# CPLD.net
KiCad netlist of a schematic drawn in Altium Designer
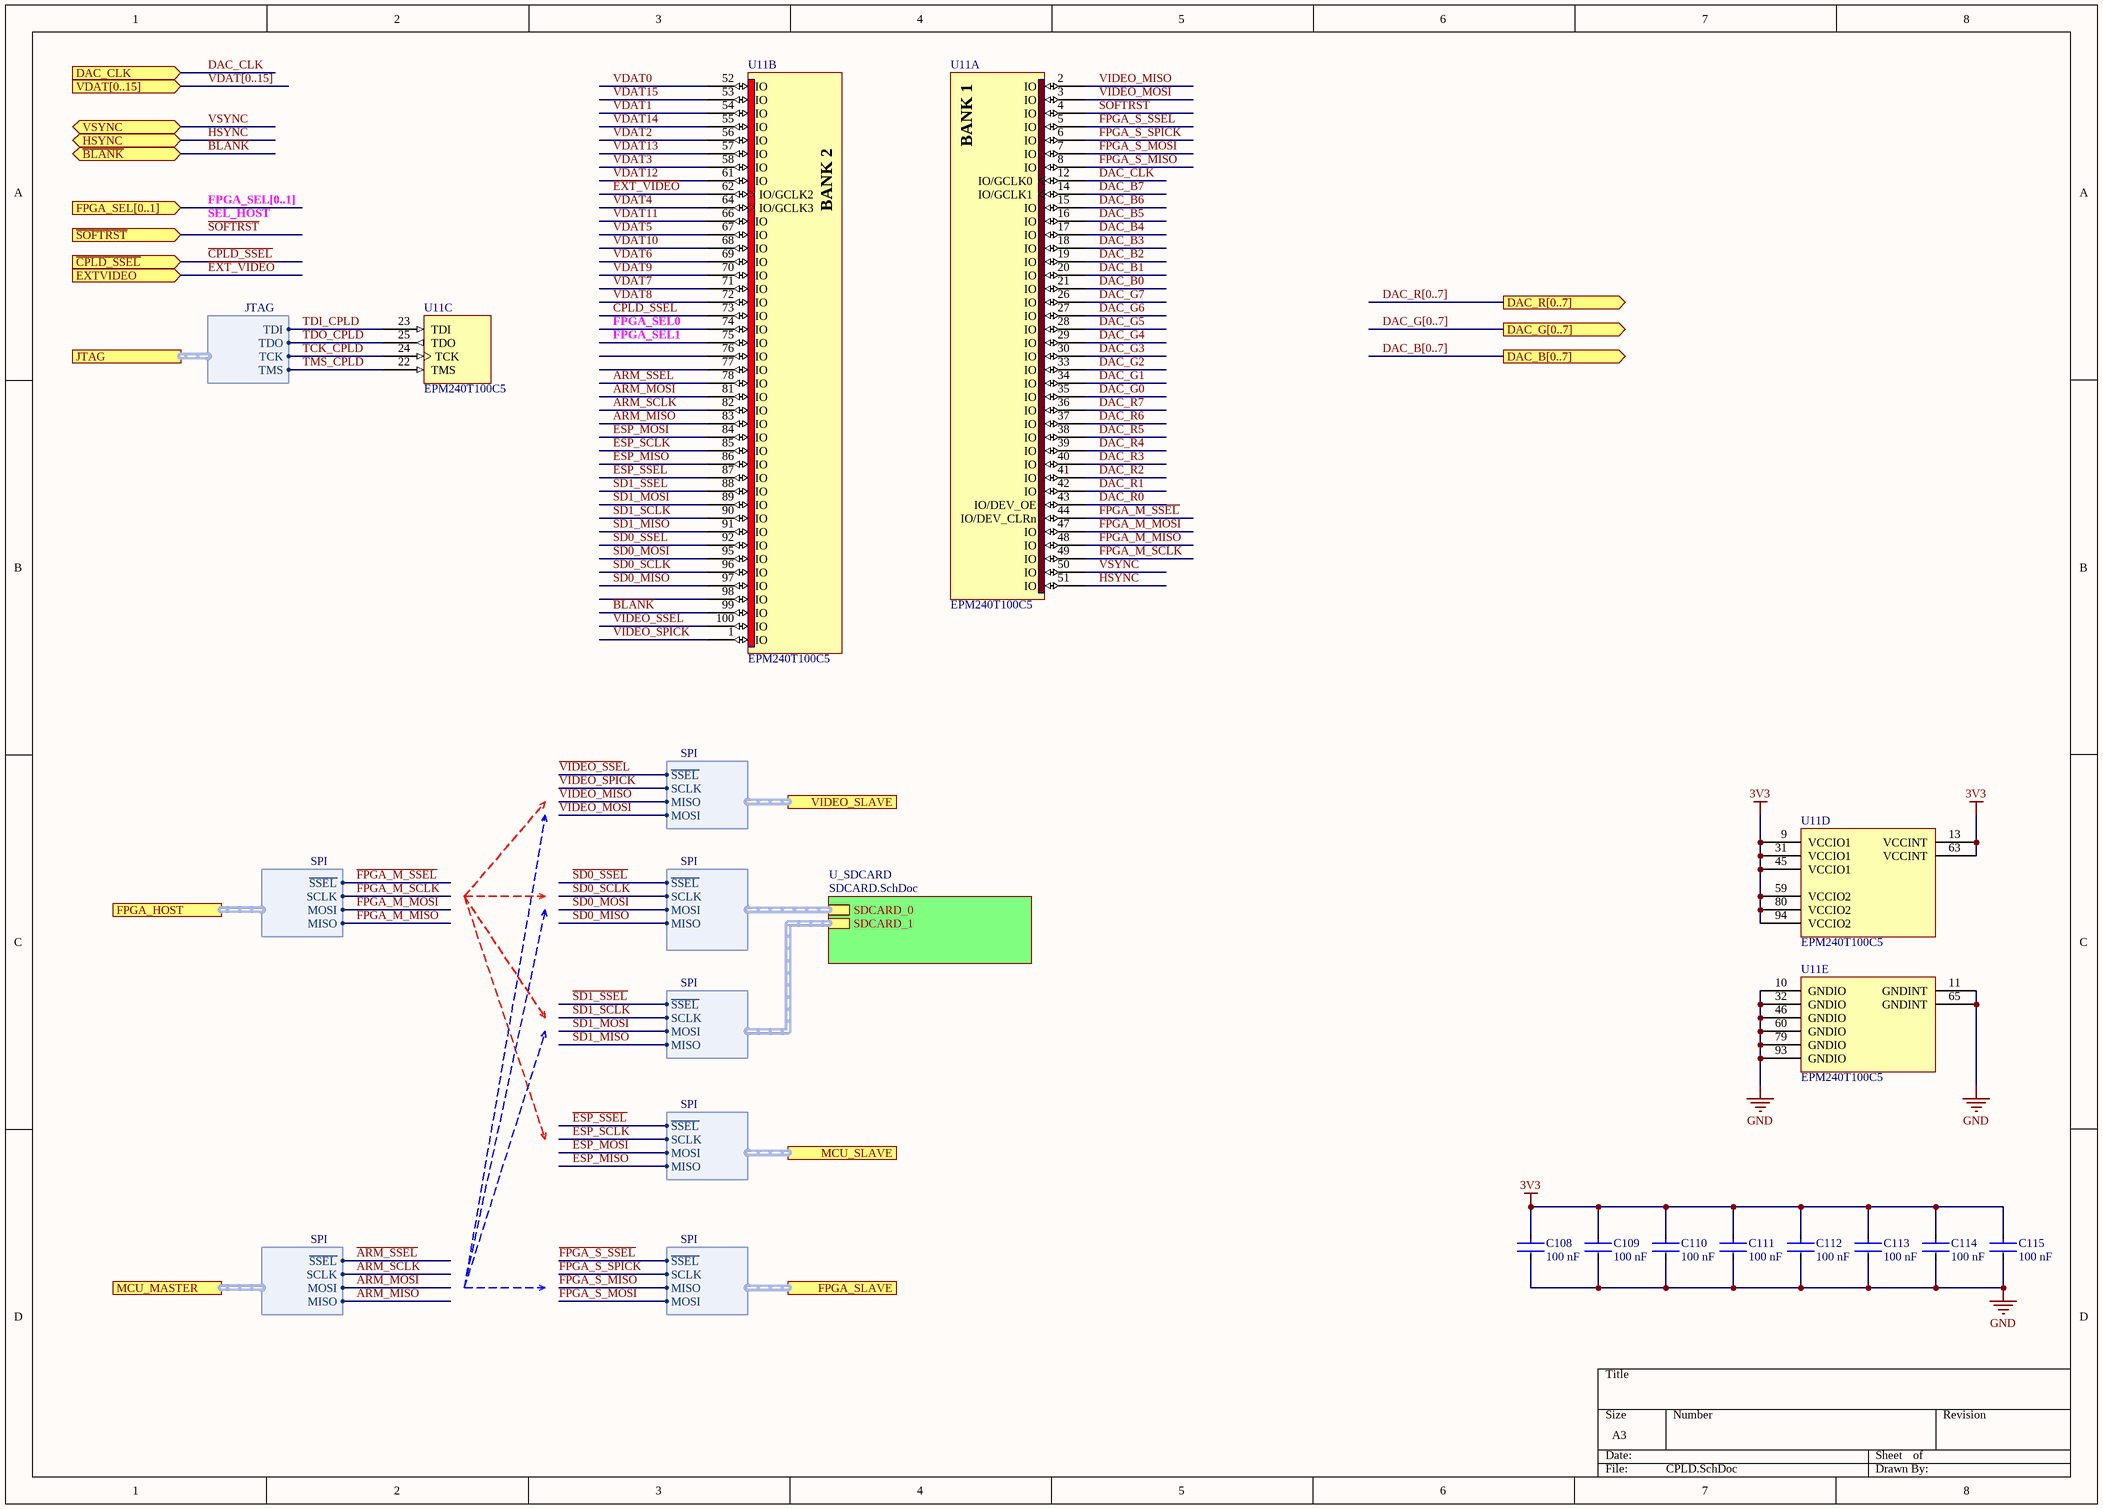
[diagram p0: CPLD.SchDoc]

(export (version "E")
  (design (tool "Eeschema 10.0.6"))
  (components
    (comp (ref "C108")
      (value "CC0805-1.5pF")
      (footprint "CC0805")
      (description "CL21 Series 0805 1.5pF 50V ±0.25pF Tolerance C0G Multilayer Ceramic Chip Capacitor")
      (fields
        (field (name "MANUFACTURER PART NUMBER") "CL21C1R5CBANNNC")
        (field (name "MANUFACTURER") "Samsung")
        (field (name "CAPACITANCE") "100 nF")
      )
      (libsource (lib "zxevo") (part "CC0805"))
    )
    (comp (ref "C109")
      (value "CC0805-1.5pF")
      (footprint "CC0805")
      (description "CL21 Series 0805 1.5pF 50V ±0.25pF Tolerance C0G Multilayer Ceramic Chip Capacitor")
      (fields
        (field (name "MANUFACTURER PART NUMBER") "CL21C1R5CBANNNC")
        (field (name "MANUFACTURER") "Samsung")
        (field (name "CAPACITANCE") "100 nF")
      )
      (libsource (lib "zxevo") (part "CC0805"))
    )
    (comp (ref "C110")
      (value "CC0805-1.5pF")
      (footprint "CC0805")
      (description "CL21 Series 0805 1.5pF 50V ±0.25pF Tolerance C0G Multilayer Ceramic Chip Capacitor")
      (fields
        (field (name "MANUFACTURER PART NUMBER") "CL21C1R5CBANNNC")
        (field (name "MANUFACTURER") "Samsung")
        (field (name "CAPACITANCE") "100 nF")
      )
      (libsource (lib "zxevo") (part "CC0805"))
    )
    (comp (ref "C111")
      (value "CC0805-1.5pF")
      (footprint "CC0805")
      (description "CL21 Series 0805 1.5pF 50V ±0.25pF Tolerance C0G Multilayer Ceramic Chip Capacitor")
      (fields
        (field (name "MANUFACTURER PART NUMBER") "CL21C1R5CBANNNC")
        (field (name "MANUFACTURER") "Samsung")
        (field (name "CAPACITANCE") "100 nF")
      )
      (libsource (lib "zxevo") (part "CC0805"))
    )
    (comp (ref "C112")
      (value "CC0805-1.5pF")
      (footprint "CC0805")
      (description "CL21 Series 0805 1.5pF 50V ±0.25pF Tolerance C0G Multilayer Ceramic Chip Capacitor")
      (fields
        (field (name "MANUFACTURER PART NUMBER") "CL21C1R5CBANNNC")
        (field (name "MANUFACTURER") "Samsung")
        (field (name "CAPACITANCE") "100 nF")
      )
      (libsource (lib "zxevo") (part "CC0805"))
    )
    (comp (ref "C113")
      (value "CC0805-1.5pF")
      (footprint "CC0805")
      (description "CL21 Series 0805 1.5pF 50V ±0.25pF Tolerance C0G Multilayer Ceramic Chip Capacitor")
      (fields
        (field (name "MANUFACTURER PART NUMBER") "CL21C1R5CBANNNC")
        (field (name "MANUFACTURER") "Samsung")
        (field (name "CAPACITANCE") "100 nF")
      )
      (libsource (lib "zxevo") (part "CC0805"))
    )
    (comp (ref "C114")
      (value "CC0805-1.5pF")
      (footprint "CC0805")
      (description "CL21 Series 0805 1.5pF 50V ±0.25pF Tolerance C0G Multilayer Ceramic Chip Capacitor")
      (fields
        (field (name "MANUFACTURER PART NUMBER") "CL21C1R5CBANNNC")
        (field (name "MANUFACTURER") "Samsung")
        (field (name "CAPACITANCE") "100 nF")
      )
      (libsource (lib "zxevo") (part "CC0805"))
    )
    (comp (ref "C115")
      (value "CC0805-1.5pF")
      (footprint "CC0805")
      (description "CL21 Series 0805 1.5pF 50V ±0.25pF Tolerance C0G Multilayer Ceramic Chip Capacitor")
      (fields
        (field (name "MANUFACTURER PART NUMBER") "CL21C1R5CBANNNC")
        (field (name "MANUFACTURER") "Samsung")
        (field (name "CAPACITANCE") "100 nF")
      )
      (libsource (lib "zxevo") (part "CC0805"))
    )
    (comp (ref "U11")
      (value "EPM240T100C5")
      (footprint "TQFP100_M")
      (fields (field (name "MANUFACTURER") "Intel Altera"))
      (libsource (lib "zxevo") (part "EPM240T100C5"))
    )
  )
  (nets
    (net (code "3") (name "/ARM_MISO") (class "Default")
      (node (ref "U11") (pin "83") (pinfunction "IO_83") (pintype "bidirectional"))
    )
    (net (code "4") (name "/ARM_MOSI") (class "Default")
      (node (ref "U11") (pin "81") (pinfunction "IO_81") (pintype "bidirectional"))
    )
    (net (code "5") (name "/ARM_SCLK") (class "Default")
      (node (ref "U11") (pin "82") (pinfunction "IO_82") (pintype "bidirectional"))
    )
    (net (code "6") (name "/DAC_B0") (class "Default")
      (node (ref "U11") (pin "21") (pinfunction "IO_21") (pintype "bidirectional"))
    )
    (net (code "7") (name "/DAC_B1") (class "Default")
      (node (ref "U11") (pin "20") (pinfunction "IO_20") (pintype "bidirectional"))
    )
    (net (code "8") (name "/DAC_B2") (class "Default")
      (node (ref "U11") (pin "19") (pinfunction "IO_19") (pintype "bidirectional"))
    )
    (net (code "9") (name "/DAC_B3") (class "Default")
      (node (ref "U11") (pin "18") (pinfunction "IO_18") (pintype "bidirectional"))
    )
    (net (code "10") (name "/DAC_B4") (class "Default")
      (node (ref "U11") (pin "17") (pinfunction "IO_17") (pintype "bidirectional"))
    )
    (net (code "11") (name "/DAC_B5") (class "Default")
      (node (ref "U11") (pin "16") (pinfunction "IO_16") (pintype "bidirectional"))
    )
    (net (code "12") (name "/DAC_B6") (class "Default")
      (node (ref "U11") (pin "15") (pinfunction "IO_15") (pintype "bidirectional"))
    )
    (net (code "13") (name "/DAC_B7") (class "Default")
      (node (ref "U11") (pin "14") (pinfunction "IO/GCLK1_14") (pintype "bidirectional"))
    )
    (net (code "15") (name "/DAC_CLK") (class "Default")
      (node (ref "U11") (pin "12") (pinfunction "IO/GCLK0_12") (pintype "bidirectional"))
    )
    (net (code "16") (name "/DAC_G0") (class "Default")
      (node (ref "U11") (pin "35") (pinfunction "IO_35") (pintype "bidirectional"))
    )
    (net (code "17") (name "/DAC_G1") (class "Default")
      (node (ref "U11") (pin "34") (pinfunction "IO_34") (pintype "bidirectional"))
    )
    (net (code "18") (name "/DAC_G2") (class "Default")
      (node (ref "U11") (pin "33") (pinfunction "IO_33") (pintype "bidirectional"))
    )
    (net (code "19") (name "/DAC_G3") (class "Default")
      (node (ref "U11") (pin "30") (pinfunction "IO_30") (pintype "bidirectional"))
    )
    (net (code "20") (name "/DAC_G4") (class "Default")
      (node (ref "U11") (pin "29") (pinfunction "IO_29") (pintype "bidirectional"))
    )
    (net (code "21") (name "/DAC_G5") (class "Default")
      (node (ref "U11") (pin "28") (pinfunction "IO_28") (pintype "bidirectional"))
    )
    (net (code "22") (name "/DAC_G6") (class "Default")
      (node (ref "U11") (pin "27") (pinfunction "IO_27") (pintype "bidirectional"))
    )
    (net (code "23") (name "/DAC_G7") (class "Default")
      (node (ref "U11") (pin "26") (pinfunction "IO_26") (pintype "bidirectional"))
    )
    (net (code "25") (name "/DAC_R0") (class "Default")
      (node (ref "U11") (pin "43") (pinfunction "IO/DEV_OE_43") (pintype "bidirectional"))
    )
    (net (code "26") (name "/DAC_R1") (class "Default")
      (node (ref "U11") (pin "42") (pinfunction "IO_42") (pintype "bidirectional"))
    )
    (net (code "27") (name "/DAC_R2") (class "Default")
      (node (ref "U11") (pin "41") (pinfunction "IO_41") (pintype "bidirectional"))
    )
    (net (code "28") (name "/DAC_R3") (class "Default")
      (node (ref "U11") (pin "40") (pinfunction "IO_40") (pintype "bidirectional"))
    )
    (net (code "29") (name "/DAC_R4") (class "Default")
      (node (ref "U11") (pin "39") (pinfunction "IO_39") (pintype "bidirectional"))
    )
    (net (code "30") (name "/DAC_R5") (class "Default")
      (node (ref "U11") (pin "38") (pinfunction "IO_38") (pintype "bidirectional"))
    )
    (net (code "31") (name "/DAC_R6") (class "Default")
      (node (ref "U11") (pin "37") (pinfunction "IO_37") (pintype "bidirectional"))
    )
    (net (code "32") (name "/DAC_R7") (class "Default")
      (node (ref "U11") (pin "36") (pinfunction "IO_36") (pintype "bidirectional"))
    )
    (net (code "34") (name "/ESP_MISO") (class "Default")
      (node (ref "U11") (pin "86") (pinfunction "IO_86") (pintype "bidirectional"))
    )
    (net (code "35") (name "/ESP_MOSI") (class "Default")
      (node (ref "U11") (pin "84") (pinfunction "IO_84") (pintype "bidirectional"))
    )
    (net (code "36") (name "/ESP_SCLK") (class "Default")
      (node (ref "U11") (pin "85") (pinfunction "IO_85") (pintype "bidirectional"))
    )
    (net (code "37") (name "/FPGA_M_MISO") (class "Default")
      (node (ref "U11") (pin "48") (pinfunction "IO_48") (pintype "bidirectional"))
    )
    (net (code "38") (name "/FPGA_M_MOSI") (class "Default")
      (node (ref "U11") (pin "47") (pinfunction "IO_47") (pintype "bidirectional"))
    )
    (net (code "39") (name "/FPGA_M_SCLK") (class "Default")
      (node (ref "U11") (pin "49") (pinfunction "IO_49") (pintype "bidirectional"))
    )
    (net (code "40") (name "/FPGA_SEL0") (class "Default")
      (node (ref "U11") (pin "74") (pinfunction "IO_74") (pintype "bidirectional"))
    )
    (net (code "41") (name "/FPGA_SEL1") (class "Default")
      (node (ref "U11") (pin "75") (pinfunction "IO_75") (pintype "bidirectional"))
    )
    (net (code "43") (name "/FPGA_S_MISO") (class "Default")
      (node (ref "U11") (pin "8") (pinfunction "IO_8") (pintype "bidirectional"))
    )
    (net (code "44") (name "/FPGA_S_MOSI") (class "Default")
      (node (ref "U11") (pin "7") (pinfunction "IO_7") (pintype "bidirectional"))
    )
    (net (code "45") (name "/FPGA_S_SPICK") (class "Default")
      (node (ref "U11") (pin "6") (pinfunction "IO_6") (pintype "bidirectional"))
    )
    (net (code "46") (name "/HSYNC") (class "Default")
      (node (ref "U11") (pin "51") (pinfunction "IO_51") (pintype "bidirectional"))
    )
    (net (code "47") (name "/SD0_MISO") (class "Default")
      (node (ref "U11") (pin "97") (pinfunction "IO_97") (pintype "bidirectional"))
    )
    (net (code "48") (name "/SD0_MOSI") (class "Default")
      (node (ref "U11") (pin "95") (pinfunction "IO_95") (pintype "bidirectional"))
    )
    (net (code "49") (name "/SD0_SCLK") (class "Default")
      (node (ref "U11") (pin "96") (pinfunction "IO_96") (pintype "bidirectional"))
    )
    (net (code "50") (name "/SD1_MISO") (class "Default")
      (node (ref "U11") (pin "91") (pinfunction "IO_91") (pintype "bidirectional"))
    )
    (net (code "51") (name "/SD1_MOSI") (class "Default")
      (node (ref "U11") (pin "89") (pinfunction "IO_89") (pintype "bidirectional"))
    )
    (net (code "52") (name "/SD1_SCLK") (class "Default")
      (node (ref "U11") (pin "90") (pinfunction "IO_90") (pintype "bidirectional"))
    )
    (net (code "54") (name "/TCK_CPLD") (class "Default")
      (node (ref "U11") (pin "24") (pinfunction "TCK_24") (pintype "input"))
    )
    (net (code "55") (name "/TDI_CPLD") (class "Default")
      (node (ref "U11") (pin "23") (pinfunction "TDI_23") (pintype "input"))
    )
    (net (code "56") (name "/TDO_CPLD") (class "Default")
      (node (ref "U11") (pin "25") (pinfunction "TDO_25") (pintype "output"))
    )
    (net (code "57") (name "/TMS_CPLD") (class "Default")
      (node (ref "U11") (pin "22") (pinfunction "TMS_22") (pintype "input"))
    )
    (net (code "58") (name "/VDAT0") (class "Default")
      (node (ref "U11") (pin "52") (pinfunction "IO_52") (pintype "bidirectional"))
    )
    (net (code "59") (name "/VDAT1") (class "Default")
      (node (ref "U11") (pin "54") (pinfunction "IO_54") (pintype "bidirectional"))
    )
    (net (code "60") (name "/VDAT2") (class "Default")
      (node (ref "U11") (pin "56") (pinfunction "IO_56") (pintype "bidirectional"))
    )
    (net (code "61") (name "/VDAT3") (class "Default")
      (node (ref "U11") (pin "58") (pinfunction "IO_58") (pintype "bidirectional"))
    )
    (net (code "62") (name "/VDAT4") (class "Default")
      (node (ref "U11") (pin "64") (pinfunction "IO/GCLK3_64") (pintype "bidirectional"))
    )
    (net (code "63") (name "/VDAT5") (class "Default")
      (node (ref "U11") (pin "67") (pinfunction "IO_67") (pintype "bidirectional"))
    )
    (net (code "64") (name "/VDAT6") (class "Default")
      (node (ref "U11") (pin "69") (pinfunction "IO_69") (pintype "bidirectional"))
    )
    (net (code "65") (name "/VDAT7") (class "Default")
      (node (ref "U11") (pin "71") (pinfunction "IO_71") (pintype "bidirectional"))
    )
    (net (code "66") (name "/VDAT8") (class "Default")
      (node (ref "U11") (pin "72") (pinfunction "IO_72") (pintype "bidirectional"))
    )
    (net (code "67") (name "/VDAT9") (class "Default")
      (node (ref "U11") (pin "70") (pinfunction "IO_70") (pintype "bidirectional"))
    )
    (net (code "68") (name "/VDAT10") (class "Default")
      (node (ref "U11") (pin "68") (pinfunction "IO_68") (pintype "bidirectional"))
    )
    (net (code "69") (name "/VDAT11") (class "Default")
      (node (ref "U11") (pin "66") (pinfunction "IO_66") (pintype "bidirectional"))
    )
    (net (code "70") (name "/VDAT12") (class "Default")
      (node (ref "U11") (pin "61") (pinfunction "IO_61") (pintype "bidirectional"))
    )
    (net (code "71") (name "/VDAT13") (class "Default")
      (node (ref "U11") (pin "57") (pinfunction "IO_57") (pintype "bidirectional"))
    )
    (net (code "72") (name "/VDAT14") (class "Default")
      (node (ref "U11") (pin "55") (pinfunction "IO_55") (pintype "bidirectional"))
    )
    (net (code "73") (name "/VDAT15") (class "Default")
      (node (ref "U11") (pin "53") (pinfunction "IO_53") (pintype "bidirectional"))
    )
    (net (code "75") (name "/VIDEO_MISO") (class "Default")
      (node (ref "U11") (pin "2") (pinfunction "IO_2") (pintype "bidirectional"))
    )
    (net (code "76") (name "/VIDEO_MOSI") (class "Default")
      (node (ref "U11") (pin "3") (pinfunction "IO_3") (pintype "bidirectional"))
    )
    (net (code "77") (name "/VIDEO_SPICK") (class "Default")
      (node (ref "U11") (pin "1") (pinfunction "IO_1") (pintype "bidirectional"))
    )
    (net (code "78") (name "/VSYNC") (class "Default")
      (node (ref "U11") (pin "50") (pinfunction "IO_50") (pintype "bidirectional"))
    )
    (net (code "81") (name "/~{ARM_SSEL}") (class "Default")
      (node (ref "U11") (pin "78") (pinfunction "IO_78") (pintype "bidirectional"))
    )
    (net (code "82") (name "/~{BLANK}") (class "Default")
      (node (ref "U11") (pin "99") (pinfunction "IO_99") (pintype "bidirectional"))
    )
    (net (code "83") (name "/~{CPLD_SSEL}") (class "Default")
      (node (ref "U11") (pin "73") (pinfunction "IO_73") (pintype "bidirectional"))
    )
    (net (code "84") (name "/~{ESP_SSEL}") (class "Default")
      (node (ref "U11") (pin "87") (pinfunction "IO_87") (pintype "bidirectional"))
    )
    (net (code "85") (name "/~{EXT_VIDEO}") (class "Default")
      (node (ref "U11") (pin "62") (pinfunction "IO/GCLK2_62") (pintype "bidirectional"))
    )
    (net (code "86") (name "/~{FPGA_M_SSEL}") (class "Default")
      (node (ref "U11") (pin "44") (pinfunction "IO/DEV_CLRn_44") (pintype "bidirectional"))
    )
    (net (code "87") (name "/~{FPGA_S_SSEL}") (class "Default")
      (node (ref "U11") (pin "5") (pinfunction "IO_5") (pintype "bidirectional"))
    )
    (net (code "88") (name "/~{SD0_SSEL}") (class "Default")
      (node (ref "U11") (pin "92") (pinfunction "IO_92") (pintype "bidirectional"))
    )
    (net (code "89") (name "/~{SD1_SSEL}") (class "Default")
      (node (ref "U11") (pin "88") (pinfunction "IO_88") (pintype "bidirectional"))
    )
    (net (code "90") (name "/~{SOFTRST}") (class "Default")
      (node (ref "U11") (pin "4") (pinfunction "IO_4") (pintype "bidirectional"))
    )
    (net (code "91") (name "/~{VIDEO_SSE}L") (class "Default")
      (node (ref "U11") (pin "100") (pinfunction "IO_100") (pintype "bidirectional"))
    )
    (net (code "92") (name "3V3") (class "Default")
      (node (ref "C108") (pin "1") (pinfunction "1_1") (pintype "passive"))
      (node (ref "C109") (pin "1") (pinfunction "1_1") (pintype "passive"))
      (node (ref "C110") (pin "1") (pinfunction "1_1") (pintype "passive"))
      (node (ref "C111") (pin "1") (pinfunction "1_1") (pintype "passive"))
      (node (ref "C112") (pin "1") (pinfunction "1_1") (pintype "passive"))
      (node (ref "C113") (pin "1") (pinfunction "1_1") (pintype "passive"))
      (node (ref "C114") (pin "1") (pinfunction "1_1") (pintype "passive"))
      (node (ref "C115") (pin "1") (pinfunction "1_1") (pintype "passive"))
      (node (ref "U11") (pin "13") (pinfunction "VCCINT_13") (pintype "power_in"))
      (node (ref "U11") (pin "31") (pinfunction "VCCIO1_31") (pintype "power_in"))
      (node (ref "U11") (pin "45") (pinfunction "VCCIO1_45") (pintype "power_in"))
      (node (ref "U11") (pin "59") (pinfunction "VCCIO2_59") (pintype "power_in"))
      (node (ref "U11") (pin "63") (pinfunction "VCCINT_63") (pintype "power_in"))
      (node (ref "U11") (pin "80") (pinfunction "VCCIO2_80") (pintype "power_in"))
      (node (ref "U11") (pin "9") (pinfunction "VCCIO1_9") (pintype "power_in"))
      (node (ref "U11") (pin "94") (pinfunction "VCCIO2_94") (pintype "power_in"))
    )
    (net (code "93") (name "GND") (class "Default")
      (node (ref "C108") (pin "2") (pinfunction "2_2") (pintype "passive"))
      (node (ref "C109") (pin "2") (pinfunction "2_2") (pintype "passive"))
      (node (ref "C110") (pin "2") (pinfunction "2_2") (pintype "passive"))
      (node (ref "C111") (pin "2") (pinfunction "2_2") (pintype "passive"))
      (node (ref "C112") (pin "2") (pinfunction "2_2") (pintype "passive"))
      (node (ref "C113") (pin "2") (pinfunction "2_2") (pintype "passive"))
      (node (ref "C114") (pin "2") (pinfunction "2_2") (pintype "passive"))
      (node (ref "C115") (pin "2") (pinfunction "2_2") (pintype "passive"))
      (node (ref "U11") (pin "10") (pinfunction "GNDIO_10") (pintype "power_in"))
      (node (ref "U11") (pin "11") (pinfunction "GNDINT_11") (pintype "power_in"))
      (node (ref "U11") (pin "32") (pinfunction "GNDIO_32") (pintype "power_in"))
      (node (ref "U11") (pin "46") (pinfunction "GNDIO_46") (pintype "power_in"))
      (node (ref "U11") (pin "60") (pinfunction "GNDIO_60") (pintype "power_in"))
      (node (ref "U11") (pin "65") (pinfunction "GNDINT_65") (pintype "power_in"))
      (node (ref "U11") (pin "79") (pinfunction "GNDIO_79") (pintype "power_in"))
      (node (ref "U11") (pin "93") (pinfunction "GNDIO_93") (pintype "power_in"))
    )
    (net (code "94") (name "unconnected-(U11B-IO-Pad76)") (class "Default")
      (node (ref "U11") (pin "76") (pinfunction "IO_76") (pintype "bidirectional"))
    )
    (net (code "95") (name "unconnected-(U11B-IO-Pad77)") (class "Default")
      (node (ref "U11") (pin "77") (pinfunction "IO_77") (pintype "bidirectional"))
    )
    (net (code "96") (name "unconnected-(U11B-IO-Pad98)") (class "Default")
      (node (ref "U11") (pin "98") (pinfunction "IO_98") (pintype "bidirectional"))
    )
  )
)
